# toilet_auto-OSH.net
KiCad netlist of a schematic drawn in EAGLE
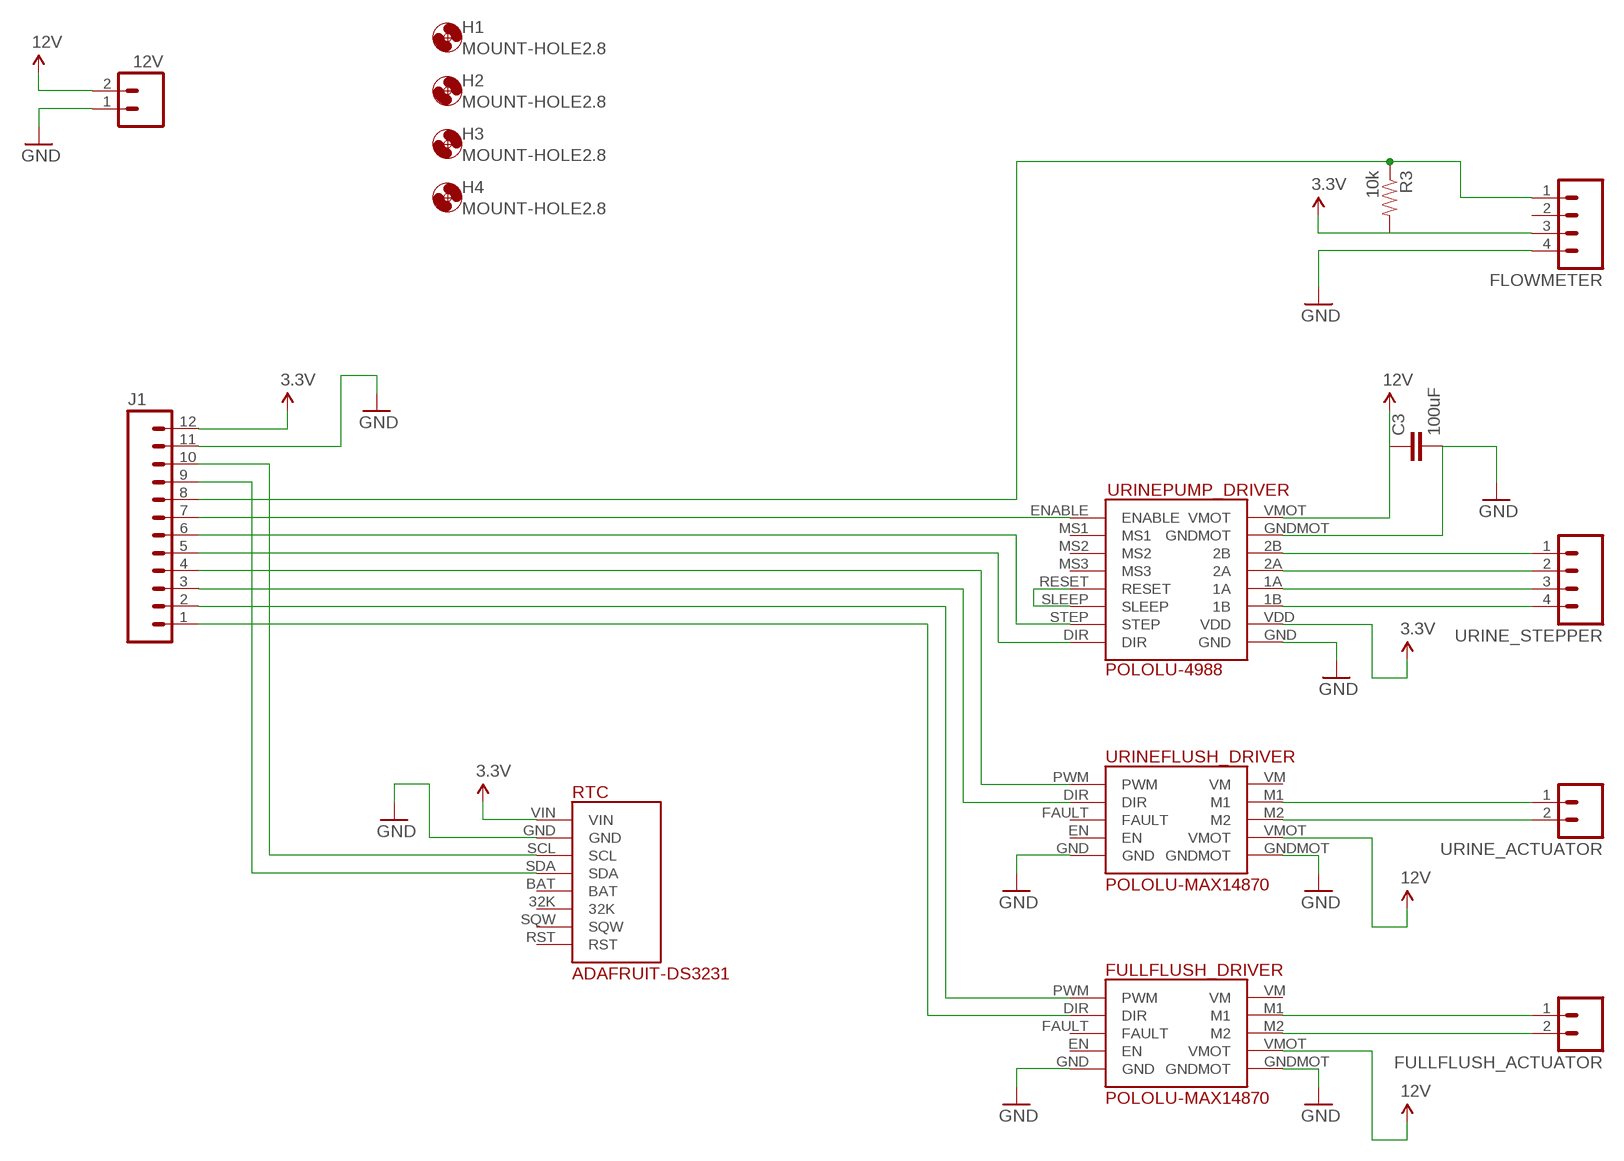
[diagram p0: schematic, sheet 1]

(export (version "E")
  (design (tool "Eeschema 10.0.6"))
  (components
    (comp (ref "12V")
      (value "M02LOCK_LONGPADS")
      (footprint "eagle-import:1X02_LOCK_LONGPADS")
      (libsource (lib "eagle-import") (part "M02LOCK_LONGPADS"))
    )
    (comp (ref "C3")
      (value "100uF")
      (footprint "eagle-import:CAP-PTH-SMALL-KIT")
      (libsource (lib "eagle-import") (part "0.1UF-50V-20%(PTH)KIT-EZ"))
    )
    (comp (ref "FLOWMETER")
      (value "M04LOCK_LONGPADS")
      (footprint "eagle-import:1X04_LOCK_LONGPADS")
      (libsource (lib "eagle-import") (part "M04LOCK_LONGPADS"))
    )
    (comp (ref "FULLFLUSH_ACTUATOR")
      (value "M02LOCK_LONGPADS")
      (footprint "eagle-import:1X02_LOCK_LONGPADS")
      (libsource (lib "eagle-import") (part "M02LOCK_LONGPADS"))
    )
    (comp (ref "FULLFLUSH_DRIVER")
      (value "POLOLU-MAX14870")
      (footprint "eagle-import:POLOLU-MAX14870")
      (libsource (lib "eagle-import") (part "POLOLU-MAX14870"))
    )
    (comp (ref "H1")
      (value "MOUNT-HOLE2.8")
      (footprint "eagle-import:2,8")
      (libsource (lib "eagle-import") (part "MOUNT-HOLE2.8"))
    )
    (comp (ref "H2")
      (value "MOUNT-HOLE2.8")
      (footprint "eagle-import:2,8")
      (libsource (lib "eagle-import") (part "MOUNT-HOLE2.8"))
    )
    (comp (ref "H3")
      (value "MOUNT-HOLE2.8")
      (footprint "eagle-import:2,8")
      (libsource (lib "eagle-import") (part "MOUNT-HOLE2.8"))
    )
    (comp (ref "H4")
      (value "MOUNT-HOLE2.8")
      (footprint "eagle-import:2,8")
      (libsource (lib "eagle-import") (part "MOUNT-HOLE2.8"))
    )
    (comp (ref "J1")
      (value "M12LOCK_LONGPADS")
      (footprint "eagle-import:1X12_LOCK_LONGPADS")
      (libsource (lib "eagle-import") (part "M12LOCK_LONGPADS"))
    )
    (comp (ref "R3")
      (value "10k")
      (footprint "eagle-import:AXIAL-0.3EZ")
      (libsource (lib "eagle-import") (part "RESISTOREZ"))
    )
    (comp (ref "RTC")
      (value "ADAFRUIT-DS3231")
      (footprint "eagle-import:ADAFRUIT-DS3231")
      (libsource (lib "eagle-import") (part "ADAFRUIT-DS3231"))
    )
    (comp (ref "URINEFLUSH_DRIVER")
      (value "POLOLU-MAX14870")
      (footprint "eagle-import:POLOLU-MAX14870")
      (libsource (lib "eagle-import") (part "POLOLU-MAX14870"))
    )
    (comp (ref "URINEPUMP_DRIVER")
      (value "POLOLU-4988")
      (footprint "eagle-import:POLOLU-4988")
      (libsource (lib "eagle-import") (part "POLOLU-4988"))
    )
    (comp (ref "URINE_ACTUATOR")
      (value "M02LOCK_LONGPADS")
      (footprint "eagle-import:1X02_LOCK_LONGPADS")
      (libsource (lib "eagle-import") (part "M02LOCK_LONGPADS"))
    )
    (comp (ref "URINE_STEPPER")
      (value "M04LOCK_LONGPADS")
      (footprint "eagle-import:1X04_LOCK_LONGPADS")
      (libsource (lib "eagle-import") (part "M04LOCK_LONGPADS"))
    )
  )
  (nets
    (net (code "1") (name "3.3V") (class "Default")
      (node (ref "FLOWMETER") (pin "3") (pinfunction "3_3") (pintype "passive"))
      (node (ref "J1") (pin "12") (pinfunction "12_12") (pintype "passive"))
      (node (ref "R3") (pin "P$2") (pinfunction "2_P$2") (pintype "passive"))
      (node (ref "RTC") (pin "VIN") (pinfunction "VIN_VIN") (pintype "bidirectional"))
      (node (ref "URINEPUMP_DRIVER") (pin "VDD") (pinfunction "VDD_VDD") (pintype "bidirectional"))
    )
    (net (code "2") (name "12V") (class "Default")
      (node (ref "12V") (pin "2") (pinfunction "2_2") (pintype "passive"))
      (node (ref "C3") (pin "1") (pinfunction "1_1") (pintype "passive"))
      (node (ref "FULLFLUSH_DRIVER") (pin "VMOT") (pinfunction "VMOT_VMOT") (pintype "bidirectional"))
      (node (ref "URINEFLUSH_DRIVER") (pin "VMOT") (pinfunction "VMOT_VMOT") (pintype "bidirectional"))
      (node (ref "URINEPUMP_DRIVER") (pin "VMOT") (pinfunction "VMOT_VMOT") (pintype "bidirectional"))
    )
    (net (code "3") (name "GND") (class "Default")
      (node (ref "12V") (pin "1") (pinfunction "1_1") (pintype "passive"))
      (node (ref "C3") (pin "2") (pinfunction "2_2") (pintype "passive"))
      (node (ref "FLOWMETER") (pin "4") (pinfunction "4_4") (pintype "passive"))
      (node (ref "FULLFLUSH_DRIVER") (pin "GND") (pinfunction "GND_GND") (pintype "bidirectional"))
      (node (ref "FULLFLUSH_DRIVER") (pin "GNDMOT") (pinfunction "GNDMOT_GNDMOT") (pintype "bidirectional"))
      (node (ref "J1") (pin "11") (pinfunction "11_11") (pintype "passive"))
      (node (ref "RTC") (pin "GND") (pinfunction "GND_GND") (pintype "bidirectional"))
      (node (ref "URINEFLUSH_DRIVER") (pin "GND") (pinfunction "GND_GND") (pintype "bidirectional"))
      (node (ref "URINEFLUSH_DRIVER") (pin "GNDMOT") (pinfunction "GNDMOT_GNDMOT") (pintype "bidirectional"))
      (node (ref "URINEPUMP_DRIVER") (pin "GND") (pinfunction "GND_GND") (pintype "bidirectional"))
      (node (ref "URINEPUMP_DRIVER") (pin "GNDMOT") (pinfunction "GNDMOT_GNDMOT") (pintype "bidirectional"))
    )
    (net (code "4") (name "Net-(FULLFLUSH_ACTUATOR-Pad1)") (class "Default")
      (node (ref "FULLFLUSH_ACTUATOR") (pin "1") (pinfunction "1_1") (pintype "passive"))
      (node (ref "FULLFLUSH_DRIVER") (pin "M1") (pinfunction "M1_M1") (pintype "bidirectional"))
    )
    (net (code "5") (name "Net-(FULLFLUSH_ACTUATOR-Pad2)") (class "Default")
      (node (ref "FULLFLUSH_ACTUATOR") (pin "2") (pinfunction "2_2") (pintype "passive"))
      (node (ref "FULLFLUSH_DRIVER") (pin "M2") (pinfunction "M2_M2") (pintype "bidirectional"))
    )
    (net (code "6") (name "Net-(FULLFLUSH_DRIVER-PadDIR)") (class "Default")
      (node (ref "FULLFLUSH_DRIVER") (pin "DIR") (pinfunction "DIR_DIR") (pintype "bidirectional"))
      (node (ref "J1") (pin "1") (pinfunction "1_1") (pintype "passive"))
    )
    (net (code "7") (name "Net-(FULLFLUSH_DRIVER-PadPWM)") (class "Default")
      (node (ref "FULLFLUSH_DRIVER") (pin "PWM") (pinfunction "PWM_PWM") (pintype "bidirectional"))
      (node (ref "J1") (pin "2") (pinfunction "2_2") (pintype "passive"))
    )
    (net (code "8") (name "Net-(J1-Pad3)") (class "Default")
      (node (ref "J1") (pin "3") (pinfunction "3_3") (pintype "passive"))
      (node (ref "URINEFLUSH_DRIVER") (pin "DIR") (pinfunction "DIR_DIR") (pintype "bidirectional"))
    )
    (net (code "9") (name "Net-(J1-Pad4)") (class "Default")
      (node (ref "J1") (pin "4") (pinfunction "4_4") (pintype "passive"))
      (node (ref "URINEFLUSH_DRIVER") (pin "PWM") (pinfunction "PWM_PWM") (pintype "bidirectional"))
    )
    (net (code "10") (name "Net-(J1-Pad5)") (class "Default")
      (node (ref "J1") (pin "5") (pinfunction "5_5") (pintype "passive"))
      (node (ref "URINEPUMP_DRIVER") (pin "DIR") (pinfunction "DIR_DIR") (pintype "bidirectional"))
    )
    (net (code "11") (name "Net-(J1-Pad6)") (class "Default")
      (node (ref "J1") (pin "6") (pinfunction "6_6") (pintype "passive"))
      (node (ref "URINEPUMP_DRIVER") (pin "STEP") (pinfunction "STEP_STEP") (pintype "bidirectional"))
    )
    (net (code "12") (name "Net-(J1-Pad7)") (class "Default")
      (node (ref "J1") (pin "7") (pinfunction "7_7") (pintype "passive"))
      (node (ref "URINEPUMP_DRIVER") (pin "ENABLE") (pinfunction "ENABLE_ENABLE") (pintype "bidirectional"))
    )
    (net (code "13") (name "Net-(J1-Pad9)") (class "Default")
      (node (ref "J1") (pin "9") (pinfunction "9_9") (pintype "passive"))
      (node (ref "RTC") (pin "SDA") (pinfunction "SDA_SDA") (pintype "bidirectional"))
    )
    (net (code "14") (name "Net-(J1-Pad10)") (class "Default")
      (node (ref "J1") (pin "10") (pinfunction "10_10") (pintype "passive"))
      (node (ref "RTC") (pin "SCL") (pinfunction "SCL_SCL") (pintype "bidirectional"))
    )
    (net (code "15") (name "Net-(R3-1)") (class "Default")
      (node (ref "FLOWMETER") (pin "1") (pinfunction "1_1") (pintype "passive"))
      (node (ref "J1") (pin "8") (pinfunction "8_8") (pintype "passive"))
      (node (ref "R3") (pin "P$1") (pinfunction "1_P$1") (pintype "passive"))
    )
    (net (code "16") (name "Net-(URINEFLUSH_DRIVER-PadM1)") (class "Default")
      (node (ref "URINEFLUSH_DRIVER") (pin "M1") (pinfunction "M1_M1") (pintype "bidirectional"))
      (node (ref "URINE_ACTUATOR") (pin "1") (pinfunction "1_1") (pintype "passive"))
    )
    (net (code "17") (name "Net-(URINEFLUSH_DRIVER-PadM2)") (class "Default")
      (node (ref "URINEFLUSH_DRIVER") (pin "M2") (pinfunction "M2_M2") (pintype "bidirectional"))
      (node (ref "URINE_ACTUATOR") (pin "2") (pinfunction "2_2") (pintype "passive"))
    )
    (net (code "18") (name "Net-(URINEPUMP_DRIVER-Pad1A)") (class "Default")
      (node (ref "URINEPUMP_DRIVER") (pin "1A") (pinfunction "1A_1A") (pintype "bidirectional"))
      (node (ref "URINE_STEPPER") (pin "3") (pinfunction "3_3") (pintype "passive"))
    )
    (net (code "19") (name "Net-(URINEPUMP_DRIVER-Pad1B)") (class "Default")
      (node (ref "URINEPUMP_DRIVER") (pin "1B") (pinfunction "1B_1B") (pintype "bidirectional"))
      (node (ref "URINE_STEPPER") (pin "4") (pinfunction "4_4") (pintype "passive"))
    )
    (net (code "20") (name "Net-(URINEPUMP_DRIVER-Pad2A)") (class "Default")
      (node (ref "URINEPUMP_DRIVER") (pin "2A") (pinfunction "2A_2A") (pintype "bidirectional"))
      (node (ref "URINE_STEPPER") (pin "2") (pinfunction "2_2") (pintype "passive"))
    )
    (net (code "21") (name "Net-(URINEPUMP_DRIVER-Pad2B)") (class "Default")
      (node (ref "URINEPUMP_DRIVER") (pin "2B") (pinfunction "2B_2B") (pintype "bidirectional"))
      (node (ref "URINE_STEPPER") (pin "1") (pinfunction "1_1") (pintype "passive"))
    )
    (net (code "22") (name "Net-(URINEPUMP_DRIVER-PadRESET)") (class "Default")
      (node (ref "URINEPUMP_DRIVER") (pin "RESET") (pinfunction "RESET_RESET") (pintype "bidirectional"))
      (node (ref "URINEPUMP_DRIVER") (pin "SLEEP") (pinfunction "SLEEP_SLEEP") (pintype "bidirectional"))
    )
    (net (code "23") (name "unconnected-(FLOWMETER-Pad2)") (class "Default")
      (node (ref "FLOWMETER") (pin "2") (pinfunction "2_2") (pintype "passive"))
    )
    (net (code "24") (name "unconnected-(FULLFLUSH_DRIVER-PadEN)") (class "Default")
      (node (ref "FULLFLUSH_DRIVER") (pin "EN") (pinfunction "EN_EN") (pintype "bidirectional"))
    )
    (net (code "25") (name "unconnected-(FULLFLUSH_DRIVER-PadFAULT)") (class "Default")
      (node (ref "FULLFLUSH_DRIVER") (pin "FAULT") (pinfunction "FAULT_FAULT") (pintype "bidirectional"))
    )
    (net (code "26") (name "unconnected-(FULLFLUSH_DRIVER-PadVM)") (class "Default")
      (node (ref "FULLFLUSH_DRIVER") (pin "VM") (pinfunction "VM_VM") (pintype "bidirectional"))
    )
    (net (code "27") (name "unconnected-(RTC-Pad32K)") (class "Default")
      (node (ref "RTC") (pin "32K") (pinfunction "32K_32K") (pintype "bidirectional"))
    )
    (net (code "28") (name "unconnected-(RTC-PadBAT)") (class "Default")
      (node (ref "RTC") (pin "BAT") (pinfunction "BAT_BAT") (pintype "bidirectional"))
    )
    (net (code "29") (name "unconnected-(RTC-PadRST)") (class "Default")
      (node (ref "RTC") (pin "RST") (pinfunction "RST_RST") (pintype "bidirectional"))
    )
    (net (code "30") (name "unconnected-(RTC-PadSQW)") (class "Default")
      (node (ref "RTC") (pin "SQW") (pinfunction "SQW_SQW") (pintype "bidirectional"))
    )
    (net (code "31") (name "unconnected-(URINEFLUSH_DRIVER-PadEN)") (class "Default")
      (node (ref "URINEFLUSH_DRIVER") (pin "EN") (pinfunction "EN_EN") (pintype "bidirectional"))
    )
    (net (code "32") (name "unconnected-(URINEFLUSH_DRIVER-PadFAULT)") (class "Default")
      (node (ref "URINEFLUSH_DRIVER") (pin "FAULT") (pinfunction "FAULT_FAULT") (pintype "bidirectional"))
    )
    (net (code "33") (name "unconnected-(URINEFLUSH_DRIVER-PadVM)") (class "Default")
      (node (ref "URINEFLUSH_DRIVER") (pin "VM") (pinfunction "VM_VM") (pintype "bidirectional"))
    )
    (net (code "34") (name "unconnected-(URINEPUMP_DRIVER-PadMS1)") (class "Default")
      (node (ref "URINEPUMP_DRIVER") (pin "MS1") (pinfunction "MS1_MS1") (pintype "bidirectional"))
    )
    (net (code "35") (name "unconnected-(URINEPUMP_DRIVER-PadMS2)") (class "Default")
      (node (ref "URINEPUMP_DRIVER") (pin "MS2") (pinfunction "MS2_MS2") (pintype "bidirectional"))
    )
    (net (code "36") (name "unconnected-(URINEPUMP_DRIVER-PadMS3)") (class "Default")
      (node (ref "URINEPUMP_DRIVER") (pin "MS3") (pinfunction "MS3_MS3") (pintype "bidirectional"))
    )
  )
)
